# Temperature_monitoring.net
KiCad netlist of a schematic drawn in Altium Designer
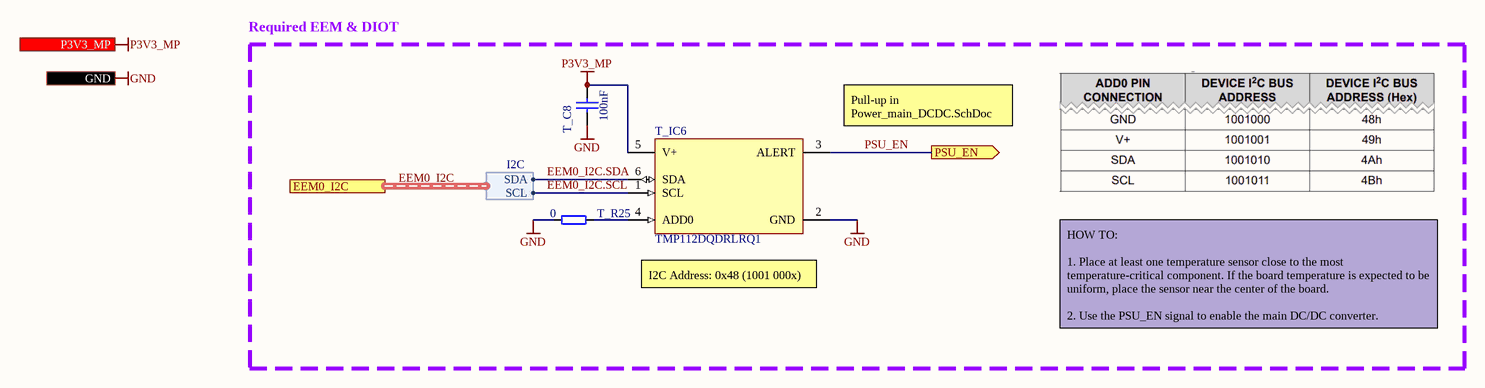
[diagram p0: Temperature_monitoring.SchDoc]

(export (version "E")
  (design (tool "Eeschema 10.0.6"))
  (components
    (comp (ref "T_C8")
      (value "100nF")
      (footprint "CAPC1005X55N")
      (description "Non-polarised capacitor")
      (fields
        (field (name "PART NUMBER") "CC0402_100NF_50V_10%_X7R")
        (field (name "VOLTAGE") "50V")
        (field (name "AUTHOR") "CERN DEM MR")
      )
      (libsource (lib "Capacitors") (part "Capacitor - non polarized"))
    )
    (comp (ref "T_IC6")
      (value "TMP112DQDRLRQ1")
      (footprint "SOTFL50P160X60-6N")
      (description "Automotive, ±0.4°C accurate I²C temperature sensor with alert option 6-SOT-5X3 -40 to 125")
      (fields (field (name "MANUFACTURER") "Texas Instruments"))
      (libsource (lib "TechnoSystem Workspace") (part "TMP112DQDRLRQ1"))
    )
    (comp (ref "T_R25")
      (value "0")
      (footprint "RESC1005X40N")
      (description "Resistor")
      (fields
        (field (name "PART NUMBER") "R0402_0R_JUMPER")
        (field (name "MANUFACTURER") "GENERIC")
        (field (name "AUTHOR") "CERN DEM JLC")
      )
      (libsource (lib "Resistors") (part "Resistor"))
    )
  )
  (nets
    (net (code "2") (name "/EEM0_I2C.SCL") (class "Default")
      (node (ref "T_IC6") (pin "1") (pinfunction "SCL_1") (pintype "input"))
    )
    (net (code "3") (name "/EEM0_I2C.SDA") (class "Default")
      (node (ref "T_IC6") (pin "6") (pinfunction "SDA_6") (pintype "bidirectional"))
    )
    (net (code "5") (name "/PSU_EN") (class "Default")
      (node (ref "T_IC6") (pin "3") (pinfunction "ALERT_3") (pintype "passive"))
    )
    (net (code "6") (name "GND") (class "Default")
      (node (ref "T_C8") (pin "1") (pinfunction "1_1") (pintype "passive"))
      (node (ref "T_IC6") (pin "2") (pinfunction "GND_2") (pintype "passive"))
      (node (ref "T_R25") (pin "1") (pinfunction "1_1") (pintype "passive"))
    )
    (net (code "7") (name "Net-(T_IC6-ADD0)") (class "Default")
      (node (ref "T_IC6") (pin "4") (pinfunction "ADD0_4") (pintype "input"))
      (node (ref "T_R25") (pin "2") (pinfunction "2_2") (pintype "passive"))
    )
    (net (code "8") (name "P3V3_MP") (class "Default")
      (node (ref "T_C8") (pin "2") (pinfunction "2_2") (pintype "passive"))
      (node (ref "T_IC6") (pin "5") (pinfunction "V+_5") (pintype "passive"))
    )
  )
)
